# LTC6811_slave_12s_rev1.net
KiCad netlist of a schematic drawn in EAGLE
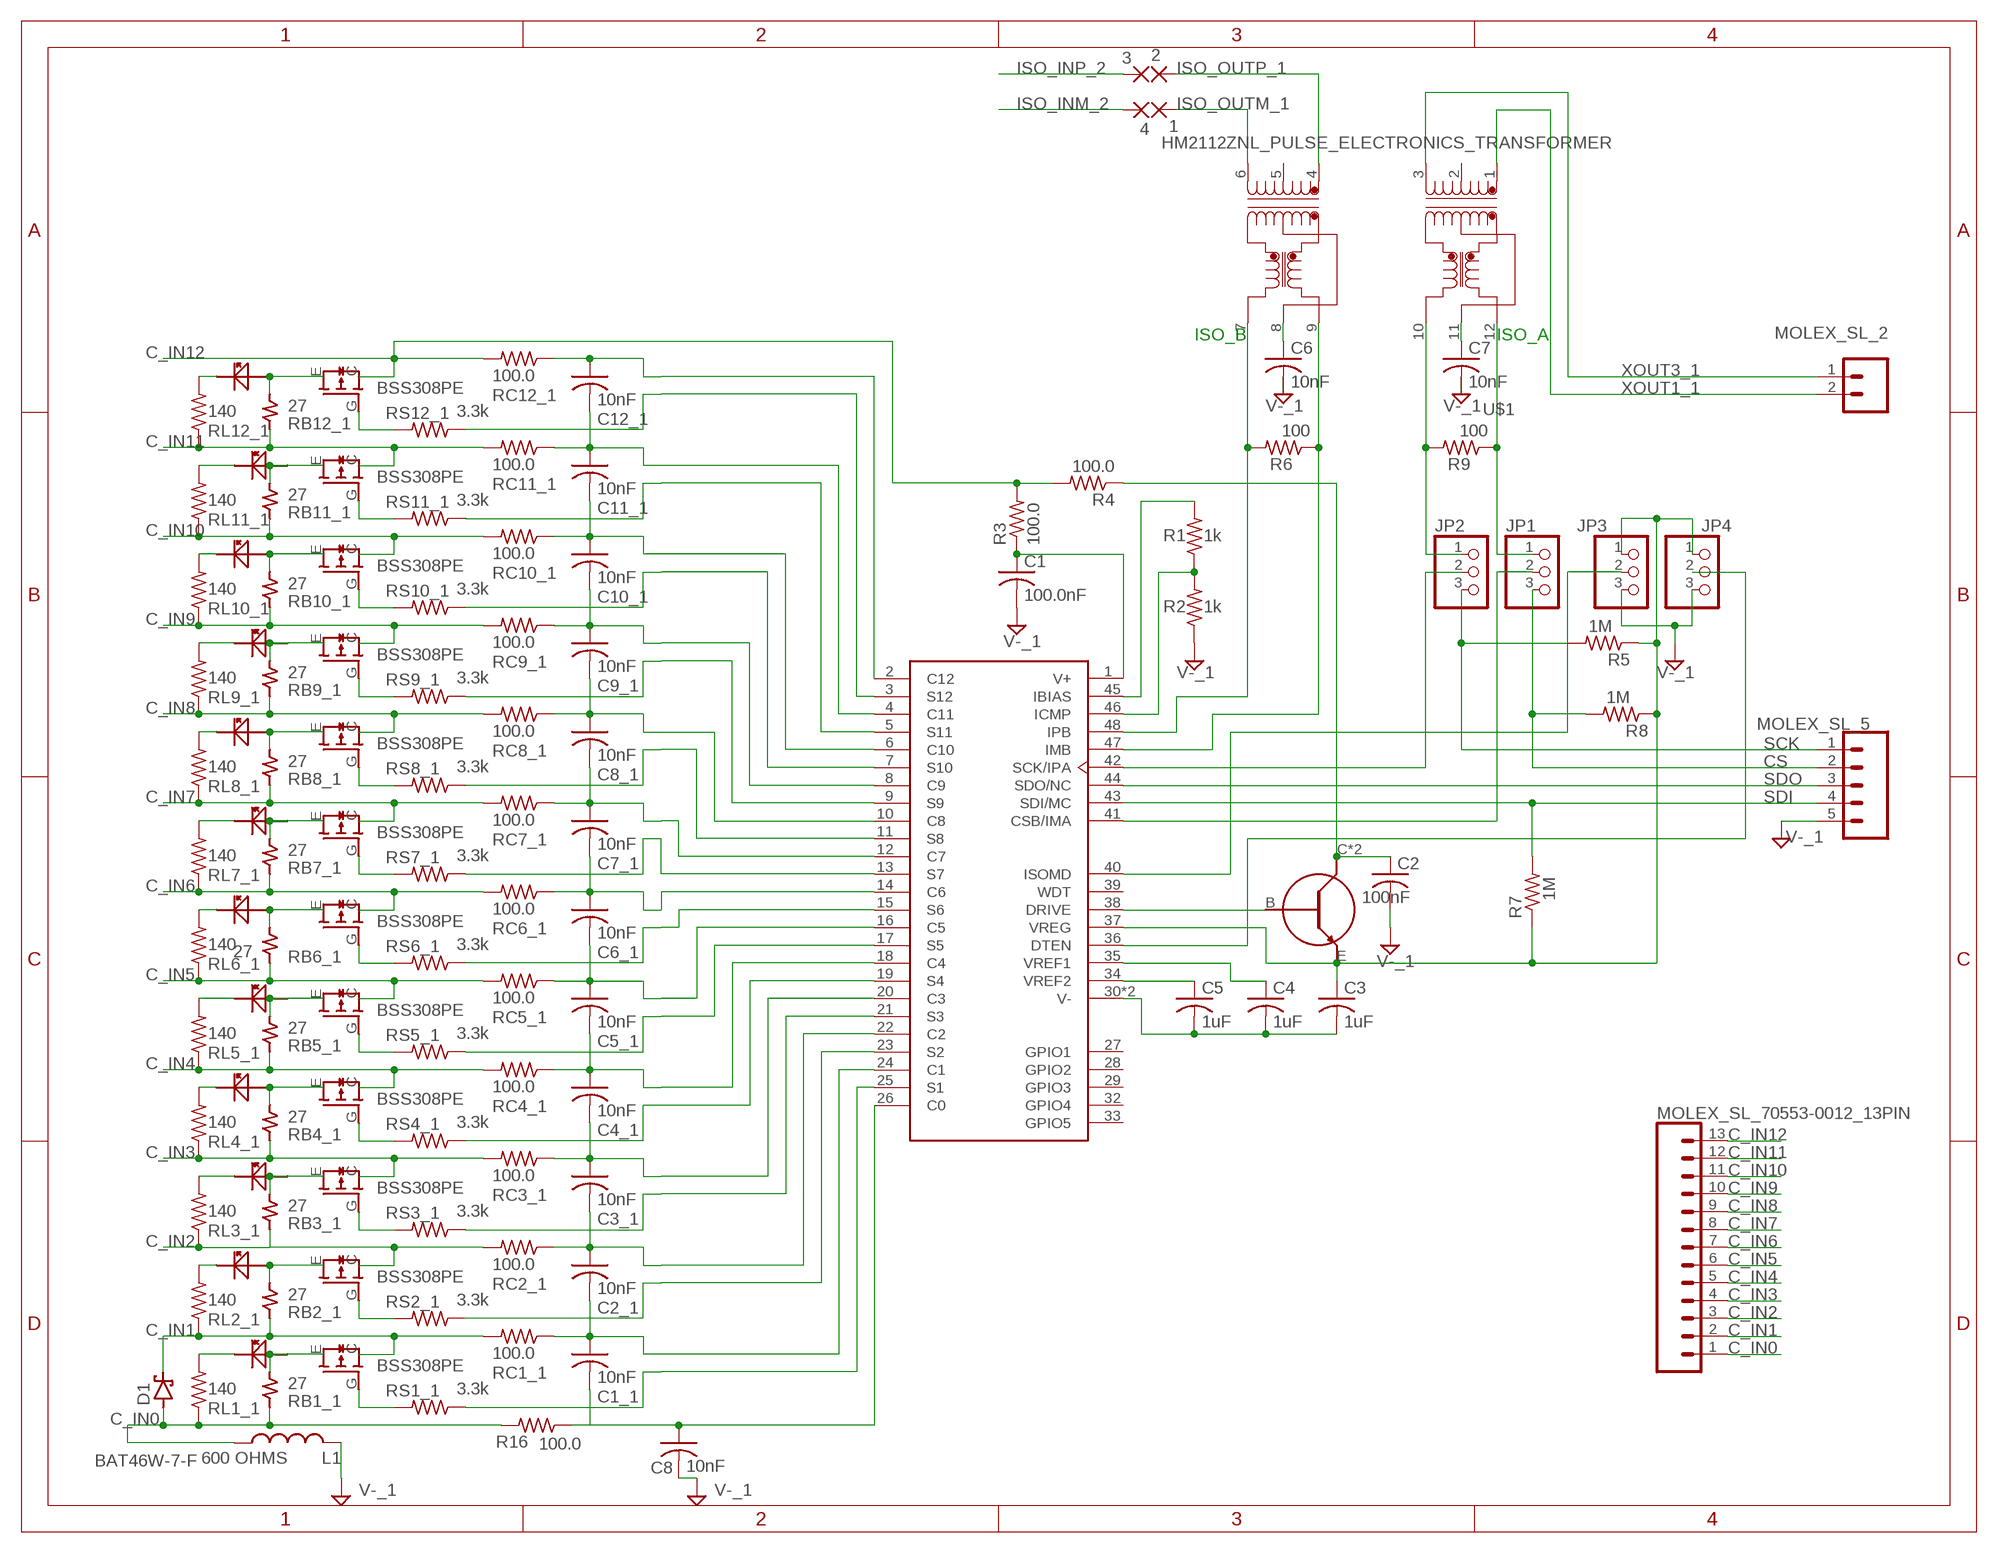
[diagram p0: schematic, sheet 1]

(export (version "E")
  (design (tool "Eeschema 10.0.6"))
  (components
    (comp (ref "1")
      (value "WIREPAD2,15/1,0")
      (footprint "eagle-import:2,15_1,0")
      (libsource (lib "eagle-import") (part "WIREPAD2,15/1,0"))
    )
    (comp (ref "2")
      (value "WIREPAD2,15/1,0")
      (footprint "eagle-import:2,15_1,0")
      (libsource (lib "eagle-import") (part "WIREPAD2,15/1,0"))
    )
    (comp (ref "3")
      (value "WIREPAD2,15/1,0")
      (footprint "eagle-import:2,15_1,0")
      (libsource (lib "eagle-import") (part "WIREPAD2,15/1,0"))
    )
    (comp (ref "4")
      (value "WIREPAD2,15/1,0")
      (footprint "eagle-import:2,15_1,0")
      (libsource (lib "eagle-import") (part "WIREPAD2,15/1,0"))
    )
    (comp (ref "C1")
      (value "100.0nF")
      (footprint "eagle-import:C0805")
      (libsource (lib "eagle-import") (part "C-USC0805"))
    )
    (comp (ref "C1_1")
      (value "10nF")
      (footprint "eagle-import:C0805")
      (libsource (lib "eagle-import") (part "C-USC0805"))
    )
    (comp (ref "C2")
      (value "100nF")
      (footprint "eagle-import:C0805")
      (libsource (lib "eagle-import") (part "C-USC0805"))
    )
    (comp (ref "C2_1")
      (value "10nF")
      (footprint "eagle-import:C0805")
      (libsource (lib "eagle-import") (part "C-USC0805"))
    )
    (comp (ref "C3")
      (value "1uF")
      (footprint "eagle-import:C0805")
      (libsource (lib "eagle-import") (part "C-USC0805"))
    )
    (comp (ref "C3_1")
      (value "10nF")
      (footprint "eagle-import:C0805")
      (libsource (lib "eagle-import") (part "C-USC0805"))
    )
    (comp (ref "C4")
      (value "1uF")
      (footprint "eagle-import:C0805")
      (libsource (lib "eagle-import") (part "C-USC0805"))
    )
    (comp (ref "C4_1")
      (value "10nF")
      (footprint "eagle-import:C0805")
      (libsource (lib "eagle-import") (part "C-USC0805"))
    )
    (comp (ref "C5")
      (value "1uF")
      (footprint "eagle-import:C0805")
      (libsource (lib "eagle-import") (part "C-USC0805"))
    )
    (comp (ref "C5_1")
      (value "10nF")
      (footprint "eagle-import:C0805")
      (libsource (lib "eagle-import") (part "C-USC0805"))
    )
    (comp (ref "C6")
      (value "10nF")
      (footprint "eagle-import:C0805")
      (libsource (lib "eagle-import") (part "C-USC0805"))
    )
    (comp (ref "C6_1")
      (value "10nF")
      (footprint "eagle-import:C0805")
      (libsource (lib "eagle-import") (part "C-USC0805"))
    )
    (comp (ref "C7")
      (value "10nF")
      (footprint "eagle-import:C0805")
      (libsource (lib "eagle-import") (part "C-USC0805"))
    )
    (comp (ref "C7_1")
      (value "10nF")
      (footprint "eagle-import:C0805")
      (libsource (lib "eagle-import") (part "C-USC0805"))
    )
    (comp (ref "C8")
      (value "10nF")
      (footprint "eagle-import:C0805")
      (libsource (lib "eagle-import") (part "C-USC0805"))
    )
    (comp (ref "C8_1")
      (value "10nF")
      (footprint "eagle-import:C0805")
      (libsource (lib "eagle-import") (part "C-USC0805"))
    )
    (comp (ref "C9_1")
      (value "10nF")
      (footprint "eagle-import:C0805")
      (libsource (lib "eagle-import") (part "C-USC0805"))
    )
    (comp (ref "C10_1")
      (value "10nF")
      (footprint "eagle-import:C0805")
      (libsource (lib "eagle-import") (part "C-USC0805"))
    )
    (comp (ref "C11_1")
      (value "10nF")
      (footprint "eagle-import:C0805")
      (libsource (lib "eagle-import") (part "C-USC0805"))
    )
    (comp (ref "C12_1")
      (value "10nF")
      (footprint "eagle-import:C0805")
      (libsource (lib "eagle-import") (part "C-USC0805"))
    )
    (comp (ref "D1")
      (value "BAT46W-7-F")
      (footprint "eagle-import:SOD123")
      (libsource (lib "eagle-import") (part "BAT46W-7-F"))
    )
    (comp (ref "DZT5551-13")
      (value "DZT5551-13")
      (footprint "eagle-import:SOT223-4")
      (libsource (lib "eagle-import") (part "DZT5551-13"))
    )
    (comp (ref "JP1")
      (value "PINHD-1X3")
      (footprint "eagle-import:1X03")
      (libsource (lib "eagle-import") (part "PINHD-1X3"))
    )
    (comp (ref "JP2")
      (value "PINHD-1X3")
      (footprint "eagle-import:1X03")
      (libsource (lib "eagle-import") (part "PINHD-1X3"))
    )
    (comp (ref "JP3")
      (value "PINHD-1X3")
      (footprint "eagle-import:1X03")
      (libsource (lib "eagle-import") (part "PINHD-1X3"))
    )
    (comp (ref "JP4")
      (value "PINHD-1X3")
      (footprint "eagle-import:1X03")
      (libsource (lib "eagle-import") (part "PINHD-1X3"))
    )
    (comp (ref "L1")
      (value "600 OHMS")
      (footprint "eagle-import:0805_COMPONENT")
      (libsource (lib "eagle-import") (part "0805_FERRITEBEAD_INDUCTOR"))
    )
    (comp (ref "LED1_3")
      (value "LED_0805")
      (footprint "eagle-import:0805_COMPONENT")
      (libsource (lib "eagle-import") (part "LED_0805"))
    )
    (comp (ref "LED1_4")
      (value "LED_0805")
      (footprint "eagle-import:0805_COMPONENT")
      (libsource (lib "eagle-import") (part "LED_0805"))
    )
    (comp (ref "LED1_5")
      (value "LED_0805")
      (footprint "eagle-import:0805_COMPONENT")
      (libsource (lib "eagle-import") (part "LED_0805"))
    )
    (comp (ref "LED1_6")
      (value "LED_0805")
      (footprint "eagle-import:0805_COMPONENT")
      (libsource (lib "eagle-import") (part "LED_0805"))
    )
    (comp (ref "LED1_7")
      (value "LED_0805")
      (footprint "eagle-import:0805_COMPONENT")
      (libsource (lib "eagle-import") (part "LED_0805"))
    )
    (comp (ref "LED1_8")
      (value "LED_0805")
      (footprint "eagle-import:0805_COMPONENT")
      (libsource (lib "eagle-import") (part "LED_0805"))
    )
    (comp (ref "LED1_9")
      (value "LED_0805")
      (footprint "eagle-import:0805_COMPONENT")
      (libsource (lib "eagle-import") (part "LED_0805"))
    )
    (comp (ref "LED1_10")
      (value "LED_0805")
      (footprint "eagle-import:0805_COMPONENT")
      (libsource (lib "eagle-import") (part "LED_0805"))
    )
    (comp (ref "LED1_11")
      (value "LED_0805")
      (footprint "eagle-import:0805_COMPONENT")
      (libsource (lib "eagle-import") (part "LED_0805"))
    )
    (comp (ref "LED1_12")
      (value "LED_0805")
      (footprint "eagle-import:0805_COMPONENT")
      (libsource (lib "eagle-import") (part "LED_0805"))
    )
    (comp (ref "LED1_13")
      (value "LED_0805")
      (footprint "eagle-import:0805_COMPONENT")
      (libsource (lib "eagle-import") (part "LED_0805"))
    )
    (comp (ref "LED1_14")
      (value "LED_0805")
      (footprint "eagle-import:0805_COMPONENT")
      (libsource (lib "eagle-import") (part "LED_0805"))
    )
    (comp (ref "MOLEX_SL_2")
      (value "CONN_02")
      (footprint "eagle-import:1X02")
      (libsource (lib "eagle-import") (part "CONN_02"))
    )
    (comp (ref "MOLEX_SL_5")
      (value "CONN_05")
      (footprint "eagle-import:1X05")
      (libsource (lib "eagle-import") (part "CONN_05"))
    )
    (comp (ref "MOLEX_SL_70553-0012_13PIN")
      (value "CONN_13")
      (footprint "eagle-import:1X13")
      (libsource (lib "eagle-import") (part "CONN_13"))
    )
    (comp (ref "R1")
      (value "1k")
      (footprint "eagle-import:R0805")
      (libsource (lib "eagle-import") (part "R-US_R0805"))
    )
    (comp (ref "R2")
      (value "1k")
      (footprint "eagle-import:R0805")
      (libsource (lib "eagle-import") (part "R-US_R0805"))
    )
    (comp (ref "R3")
      (value "100.0")
      (footprint "eagle-import:R0805")
      (libsource (lib "eagle-import") (part "R-US_R0805"))
    )
    (comp (ref "R4")
      (value "100.0")
      (footprint "eagle-import:R0805")
      (libsource (lib "eagle-import") (part "R-US_R0805"))
    )
    (comp (ref "R5")
      (value "1M")
      (footprint "eagle-import:R0805")
      (libsource (lib "eagle-import") (part "R-US_R0805"))
    )
    (comp (ref "R6")
      (value "100")
      (footprint "eagle-import:R0805")
      (libsource (lib "eagle-import") (part "R-US_R0805"))
    )
    (comp (ref "R7")
      (value "1M")
      (footprint "eagle-import:R0805")
      (libsource (lib "eagle-import") (part "R-US_R0805"))
    )
    (comp (ref "R8")
      (value "1M")
      (footprint "eagle-import:R0805")
      (libsource (lib "eagle-import") (part "R-US_R0805"))
    )
    (comp (ref "R9")
      (value "100")
      (footprint "eagle-import:R0805")
      (libsource (lib "eagle-import") (part "R-US_R0805"))
    )
    (comp (ref "R16")
      (value "100.0")
      (footprint "eagle-import:R0805")
      (libsource (lib "eagle-import") (part "R-US_R0805"))
    )
    (comp (ref "RB1_1")
      (value "27")
      (footprint "eagle-import:2817_COMPONENT")
      (libsource (lib "eagle-import") (part "2817_RESISTOR"))
    )
    (comp (ref "RB2_1")
      (value "27")
      (footprint "eagle-import:2817_COMPONENT")
      (libsource (lib "eagle-import") (part "2817_RESISTOR"))
    )
    (comp (ref "RB3_1")
      (value "27")
      (footprint "eagle-import:2817_COMPONENT")
      (libsource (lib "eagle-import") (part "2817_RESISTOR"))
    )
    (comp (ref "RB4_1")
      (value "27")
      (footprint "eagle-import:2817_COMPONENT")
      (libsource (lib "eagle-import") (part "2817_RESISTOR"))
    )
    (comp (ref "RB5_1")
      (value "27")
      (footprint "eagle-import:2817_COMPONENT")
      (libsource (lib "eagle-import") (part "2817_RESISTOR"))
    )
    (comp (ref "RB6_1")
      (value "27")
      (footprint "eagle-import:2817_COMPONENT")
      (libsource (lib "eagle-import") (part "2817_RESISTOR"))
    )
    (comp (ref "RB7_1")
      (value "27")
      (footprint "eagle-import:2817_COMPONENT")
      (libsource (lib "eagle-import") (part "2817_RESISTOR"))
    )
    (comp (ref "RB8_1")
      (value "27")
      (footprint "eagle-import:2817_COMPONENT")
      (libsource (lib "eagle-import") (part "2817_RESISTOR"))
    )
    (comp (ref "RB9_1")
      (value "27")
      (footprint "eagle-import:2817_COMPONENT")
      (libsource (lib "eagle-import") (part "2817_RESISTOR"))
    )
    (comp (ref "RB10_1")
      (value "27")
      (footprint "eagle-import:2817_COMPONENT")
      (libsource (lib "eagle-import") (part "2817_RESISTOR"))
    )
    (comp (ref "RB11_1")
      (value "27")
      (footprint "eagle-import:2817_COMPONENT")
      (libsource (lib "eagle-import") (part "2817_RESISTOR"))
    )
    (comp (ref "RB12_1")
      (value "27")
      (footprint "eagle-import:2817_COMPONENT")
      (libsource (lib "eagle-import") (part "2817_RESISTOR"))
    )
    (comp (ref "RC1_1")
      (value "100.0")
      (footprint "eagle-import:R0805")
      (libsource (lib "eagle-import") (part "R-US_R0805"))
    )
    (comp (ref "RC2_1")
      (value "100.0")
      (footprint "eagle-import:R0805")
      (libsource (lib "eagle-import") (part "R-US_R0805"))
    )
    (comp (ref "RC3_1")
      (value "100.0")
      (footprint "eagle-import:R0805")
      (libsource (lib "eagle-import") (part "R-US_R0805"))
    )
    (comp (ref "RC4_1")
      (value "100.0")
      (footprint "eagle-import:R0805")
      (libsource (lib "eagle-import") (part "R-US_R0805"))
    )
    (comp (ref "RC5_1")
      (value "100.0")
      (footprint "eagle-import:R0805")
      (libsource (lib "eagle-import") (part "R-US_R0805"))
    )
    (comp (ref "RC6_1")
      (value "100.0")
      (footprint "eagle-import:R0805")
      (libsource (lib "eagle-import") (part "R-US_R0805"))
    )
    (comp (ref "RC7_1")
      (value "100.0")
      (footprint "eagle-import:R0805")
      (libsource (lib "eagle-import") (part "R-US_R0805"))
    )
    (comp (ref "RC8_1")
      (value "100.0")
      (footprint "eagle-import:R0805")
      (libsource (lib "eagle-import") (part "R-US_R0805"))
    )
    (comp (ref "RC9_1")
      (value "100.0")
      (footprint "eagle-import:R0805")
      (libsource (lib "eagle-import") (part "R-US_R0805"))
    )
    (comp (ref "RC10_1")
      (value "100.0")
      (footprint "eagle-import:R0805")
      (libsource (lib "eagle-import") (part "R-US_R0805"))
    )
    (comp (ref "RC11_1")
      (value "100.0")
      (footprint "eagle-import:R0805")
      (libsource (lib "eagle-import") (part "R-US_R0805"))
    )
    (comp (ref "RC12_1")
      (value "100.0")
      (footprint "eagle-import:R0805")
      (libsource (lib "eagle-import") (part "R-US_R0805"))
    )
    (comp (ref "RL1_1")
      (value "140")
      (footprint "eagle-import:R0805")
      (libsource (lib "eagle-import") (part "R-US_R0805"))
    )
    (comp (ref "RL2_1")
      (value "140")
      (footprint "eagle-import:R0805")
      (libsource (lib "eagle-import") (part "R-US_R0805"))
    )
    (comp (ref "RL3_1")
      (value "140")
      (footprint "eagle-import:R0805")
      (libsource (lib "eagle-import") (part "R-US_R0805"))
    )
    (comp (ref "RL4_1")
      (value "140")
      (footprint "eagle-import:R0805")
      (libsource (lib "eagle-import") (part "R-US_R0805"))
    )
    (comp (ref "RL5_1")
      (value "140")
      (footprint "eagle-import:R0805")
      (libsource (lib "eagle-import") (part "R-US_R0805"))
    )
    (comp (ref "RL6_1")
      (value "140")
      (footprint "eagle-import:R0805")
      (libsource (lib "eagle-import") (part "R-US_R0805"))
    )
    (comp (ref "RL7_1")
      (value "140")
      (footprint "eagle-import:R0805")
      (libsource (lib "eagle-import") (part "R-US_R0805"))
    )
    (comp (ref "RL8_1")
      (value "140")
      (footprint "eagle-import:R0805")
      (libsource (lib "eagle-import") (part "R-US_R0805"))
    )
    (comp (ref "RL9_1")
      (value "140")
      (footprint "eagle-import:R0805")
      (libsource (lib "eagle-import") (part "R-US_R0805"))
    )
    (comp (ref "RL10_1")
      (value "140")
      (footprint "eagle-import:R0805")
      (libsource (lib "eagle-import") (part "R-US_R0805"))
    )
    (comp (ref "RL11_1")
      (value "140")
      (footprint "eagle-import:R0805")
      (libsource (lib "eagle-import") (part "R-US_R0805"))
    )
    (comp (ref "RL12_1")
      (value "140")
      (footprint "eagle-import:R0805")
      (libsource (lib "eagle-import") (part "R-US_R0805"))
    )
    (comp (ref "RS1_1")
      (value "3.3k")
      (footprint "eagle-import:R0805")
      (libsource (lib "eagle-import") (part "R-US_R0805"))
    )
    (comp (ref "RS2_1")
      (value "3.3k")
      (footprint "eagle-import:R0805")
      (libsource (lib "eagle-import") (part "R-US_R0805"))
    )
    (comp (ref "RS3_1")
      (value "3.3k")
      (footprint "eagle-import:R0805")
      (libsource (lib "eagle-import") (part "R-US_R0805"))
    )
    (comp (ref "RS4_1")
      (value "3.3k")
      (footprint "eagle-import:R0805")
      (libsource (lib "eagle-import") (part "R-US_R0805"))
    )
    (comp (ref "RS5_1")
      (value "3.3k")
      (footprint "eagle-import:R0805")
      (libsource (lib "eagle-import") (part "R-US_R0805"))
    )
    (comp (ref "RS6_1")
      (value "3.3k")
      (footprint "eagle-import:R0805")
      (libsource (lib "eagle-import") (part "R-US_R0805"))
    )
    (comp (ref "RS7_1")
      (value "3.3k")
      (footprint "eagle-import:R0805")
      (libsource (lib "eagle-import") (part "R-US_R0805"))
    )
    (comp (ref "RS8_1")
      (value "3.3k")
      (footprint "eagle-import:R0805")
      (libsource (lib "eagle-import") (part "R-US_R0805"))
    )
    (comp (ref "RS9_1")
      (value "3.3k")
      (footprint "eagle-import:R0805")
      (libsource (lib "eagle-import") (part "R-US_R0805"))
    )
    (comp (ref "RS10_1")
      (value "3.3k")
      (footprint "eagle-import:R0805")
      (libsource (lib "eagle-import") (part "R-US_R0805"))
    )
    (comp (ref "RS11_1")
      (value "3.3k")
      (footprint "eagle-import:R0805")
      (libsource (lib "eagle-import") (part "R-US_R0805"))
    )
    (comp (ref "RS12_1")
      (value "3.3k")
      (footprint "eagle-import:R0805")
      (libsource (lib "eagle-import") (part "R-US_R0805"))
    )
    (comp (ref "T1_3")
      (value "BSS308PEH6327")
      (footprint "eagle-import:SOT23")
      (libsource (lib "eagle-import") (part "BSS308PEH6327"))
    )
    (comp (ref "T1_4")
      (value "BSS308PEH6327")
      (footprint "eagle-import:SOT23")
      (libsource (lib "eagle-import") (part "BSS308PEH6327"))
    )
    (comp (ref "T1_5")
      (value "BSS308PEH6327")
      (footprint "eagle-import:SOT23")
      (libsource (lib "eagle-import") (part "BSS308PEH6327"))
    )
    (comp (ref "T1_6")
      (value "BSS308PEH6327")
      (footprint "eagle-import:SOT23")
      (libsource (lib "eagle-import") (part "BSS308PEH6327"))
    )
    (comp (ref "T1_7")
      (value "BSS308PEH6327")
      (footprint "eagle-import:SOT23")
      (libsource (lib "eagle-import") (part "BSS308PEH6327"))
    )
    (comp (ref "T1_8")
      (value "BSS308PEH6327")
      (footprint "eagle-import:SOT23")
      (libsource (lib "eagle-import") (part "BSS308PEH6327"))
    )
    (comp (ref "T1_9")
      (value "BSS308PEH6327")
      (footprint "eagle-import:SOT23")
      (libsource (lib "eagle-import") (part "BSS308PEH6327"))
    )
    (comp (ref "T1_10")
      (value "BSS308PEH6327")
      (footprint "eagle-import:SOT23")
      (libsource (lib "eagle-import") (part "BSS308PEH6327"))
    )
    (comp (ref "T1_11")
      (value "BSS308PEH6327")
      (footprint "eagle-import:SOT23")
      (libsource (lib "eagle-import") (part "BSS308PEH6327"))
    )
    (comp (ref "T1_12")
      (value "BSS308PEH6327")
      (footprint "eagle-import:SOT23")
      (libsource (lib "eagle-import") (part "BSS308PEH6327"))
    )
    (comp (ref "T1_13")
      (value "BSS308PEH6327")
      (footprint "eagle-import:SOT23")
      (libsource (lib "eagle-import") (part "BSS308PEH6327"))
    )
    (comp (ref "T1_14")
      (value "BSS308PEH6327")
      (footprint "eagle-import:SOT23")
      (libsource (lib "eagle-import") (part "BSS308PEH6327"))
    )
    (comp (ref "U$1")
      (value "HM2112ZNL_PULSE_ELECTRONICS_TRANSFORMER")
      (footprint "eagle-import:HM2112ZNL_12SMT")
      (libsource (lib "eagle-import") (part "HM2112ZNL_PULSE_ELECTRONICS_TRANSFORMER"))
    )
    (comp (ref "U1")
      (value "LTC6811HG-2#PBF")
      (footprint "eagle-import:LTC6811-1")
      (fields (field (name "MF") "Linear Technology/Analog"))
      (libsource (lib "eagle-import") (part "LTC6811HG-2#PBF"))
    )
  )
  (nets
    (net (code "1") (name "C2") (class "Default")
      (node (ref "C2_1") (pin "1") (pinfunction "1_1") (pintype "passive"))
      (node (ref "C3_1") (pin "2") (pinfunction "2_2") (pintype "passive"))
      (node (ref "RC2_1") (pin "1") (pinfunction "1_1") (pintype "passive"))
      (node (ref "U1") (pin "22") (pinfunction "C2_22") (pintype "input"))
    )
    (net (code "2") (name "C4") (class "Default")
      (node (ref "C4_1") (pin "1") (pinfunction "1_1") (pintype "passive"))
      (node (ref "C5_1") (pin "2") (pinfunction "2_2") (pintype "passive"))
      (node (ref "RC4_1") (pin "1") (pinfunction "1_1") (pintype "passive"))
      (node (ref "U1") (pin "18") (pinfunction "C4_18") (pintype "input"))
    )
    (net (code "3") (name "C6") (class "Default")
      (node (ref "C6_1") (pin "1") (pinfunction "1_1") (pintype "passive"))
      (node (ref "C7_1") (pin "2") (pinfunction "2_2") (pintype "passive"))
      (node (ref "RC6_1") (pin "1") (pinfunction "1_1") (pintype "passive"))
      (node (ref "U1") (pin "14") (pinfunction "C6_14") (pintype "input"))
    )
    (net (code "4") (name "C8") (class "Default")
      (node (ref "C8_1") (pin "1") (pinfunction "1_1") (pintype "passive"))
      (node (ref "C9_1") (pin "2") (pinfunction "2_2") (pintype "passive"))
      (node (ref "RC8_1") (pin "1") (pinfunction "1_1") (pintype "passive"))
      (node (ref "U1") (pin "10") (pinfunction "C8_10") (pintype "input"))
    )
    (net (code "5") (name "CS") (class "Default")
      (node (ref "JP1") (pin "3") (pinfunction "3_3") (pintype "passive"))
      (node (ref "MOLEX_SL_5") (pin "2") (pinfunction "2_2") (pintype "passive"))
      (node (ref "R8") (pin "2") (pinfunction "2_2") (pintype "passive"))
    )
    (net (code "6") (name "C_IN0") (class "Default")
      (node (ref "D1") (pin "A") (pinfunction "A_A") (pintype "passive"))
      (node (ref "L1") (pin "1") (pinfunction "1_1") (pintype "passive"))
      (node (ref "MOLEX_SL_70553-0012_13PIN") (pin "1") (pinfunction "1_1") (pintype "passive"))
      (node (ref "R16") (pin "2") (pinfunction "2_2") (pintype "passive"))
      (node (ref "RB1_1") (pin "2") (pinfunction "P$2_2") (pintype "bidirectional"))
      (node (ref "RL1_1") (pin "1") (pinfunction "1_1") (pintype "passive"))
    )
    (net (code "7") (name "C_IN1") (class "Default")
      (node (ref "D1") (pin "C") (pinfunction "C_C") (pintype "passive"))
      (node (ref "MOLEX_SL_70553-0012_13PIN") (pin "2") (pinfunction "2_2") (pintype "passive"))
      (node (ref "RB2_1") (pin "2") (pinfunction "P$2_2") (pintype "bidirectional"))
      (node (ref "RC1_1") (pin "2") (pinfunction "2_2") (pintype "passive"))
      (node (ref "RL2_1") (pin "1") (pinfunction "1_1") (pintype "passive"))
      (node (ref "T1_3") (pin "C") (pinfunction "C_C") (pintype "bidirectional"))
    )
    (net (code "8") (name "C_IN2") (class "Default")
      (node (ref "MOLEX_SL_70553-0012_13PIN") (pin "3") (pinfunction "3_3") (pintype "passive"))
      (node (ref "RB3_1") (pin "2") (pinfunction "P$2_2") (pintype "bidirectional"))
      (node (ref "RC2_1") (pin "2") (pinfunction "2_2") (pintype "passive"))
      (node (ref "RL3_1") (pin "1") (pinfunction "1_1") (pintype "passive"))
      (node (ref "T1_4") (pin "C") (pinfunction "C_C") (pintype "bidirectional"))
    )
    (net (code "9") (name "C_IN3") (class "Default")
      (node (ref "MOLEX_SL_70553-0012_13PIN") (pin "4") (pinfunction "4_4") (pintype "passive"))
      (node (ref "RB4_1") (pin "2") (pinfunction "P$2_2") (pintype "bidirectional"))
      (node (ref "RC3_1") (pin "2") (pinfunction "2_2") (pintype "passive"))
      (node (ref "RL4_1") (pin "1") (pinfunction "1_1") (pintype "passive"))
      (node (ref "T1_7") (pin "C") (pinfunction "C_C") (pintype "bidirectional"))
    )
    (net (code "10") (name "C_IN4") (class "Default")
      (node (ref "MOLEX_SL_70553-0012_13PIN") (pin "5") (pinfunction "5_5") (pintype "passive"))
      (node (ref "RB5_1") (pin "2") (pinfunction "P$2_2") (pintype "bidirectional"))
      (node (ref "RC4_1") (pin "2") (pinfunction "2_2") (pintype "passive"))
      (node (ref "RL5_1") (pin "1") (pinfunction "1_1") (pintype "passive"))
      (node (ref "T1_8") (pin "C") (pinfunction "C_C") (pintype "bidirectional"))
    )
    (net (code "11") (name "C_IN5") (class "Default")
      (node (ref "MOLEX_SL_70553-0012_13PIN") (pin "6") (pinfunction "6_6") (pintype "passive"))
      (node (ref "RB6_1") (pin "2") (pinfunction "P$2_2") (pintype "bidirectional"))
      (node (ref "RC5_1") (pin "2") (pinfunction "2_2") (pintype "passive"))
      (node (ref "RL6_1") (pin "1") (pinfunction "1_1") (pintype "passive"))
      (node (ref "T1_5") (pin "C") (pinfunction "C_C") (pintype "bidirectional"))
    )
    (net (code "12") (name "C_IN6") (class "Default")
      (node (ref "MOLEX_SL_70553-0012_13PIN") (pin "7") (pinfunction "7_7") (pintype "passive"))
      (node (ref "RB7_1") (pin "2") (pinfunction "P$2_2") (pintype "bidirectional"))
      (node (ref "RC6_1") (pin "2") (pinfunction "2_2") (pintype "passive"))
      (node (ref "RL7_1") (pin "1") (pinfunction "1_1") (pintype "passive"))
      (node (ref "T1_6") (pin "C") (pinfunction "C_C") (pintype "bidirectional"))
    )
    (net (code "13") (name "C_IN7") (class "Default")
      (node (ref "MOLEX_SL_70553-0012_13PIN") (pin "8") (pinfunction "8_8") (pintype "passive"))
      (node (ref "RB8_1") (pin "2") (pinfunction "P$2_2") (pintype "bidirectional"))
      (node (ref "RC7_1") (pin "2") (pinfunction "2_2") (pintype "passive"))
      (node (ref "RL8_1") (pin "1") (pinfunction "1_1") (pintype "passive"))
      (node (ref "T1_9") (pin "C") (pinfunction "C_C") (pintype "bidirectional"))
    )
    (net (code "14") (name "C_IN8") (class "Default")
      (node (ref "MOLEX_SL_70553-0012_13PIN") (pin "9") (pinfunction "9_9") (pintype "passive"))
      (node (ref "RB9_1") (pin "2") (pinfunction "P$2_2") (pintype "bidirectional"))
      (node (ref "RC8_1") (pin "2") (pinfunction "2_2") (pintype "passive"))
      (node (ref "RL9_1") (pin "1") (pinfunction "1_1") (pintype "passive"))
      (node (ref "T1_10") (pin "C") (pinfunction "C_C") (pintype "bidirectional"))
    )
    (net (code "15") (name "C_IN9") (class "Default")
      (node (ref "MOLEX_SL_70553-0012_13PIN") (pin "10") (pinfunction "10_10") (pintype "passive"))
      (node (ref "RB10_1") (pin "2") (pinfunction "P$2_2") (pintype "bidirectional"))
      (node (ref "RC9_1") (pin "2") (pinfunction "2_2") (pintype "passive"))
      (node (ref "RL10_1") (pin "1") (pinfunction "1_1") (pintype "passive"))
      (node (ref "T1_11") (pin "C") (pinfunction "C_C") (pintype "bidirectional"))
    )
    (net (code "16") (name "C_IN10") (class "Default")
      (node (ref "MOLEX_SL_70553-0012_13PIN") (pin "11") (pinfunction "11_11") (pintype "passive"))
      (node (ref "RB11_1") (pin "2") (pinfunction "P$2_2") (pintype "bidirectional"))
      (node (ref "RC10_1") (pin "2") (pinfunction "2_2") (pintype "passive"))
      (node (ref "RL11_1") (pin "1") (pinfunction "1_1") (pintype "passive"))
      (node (ref "T1_12") (pin "C") (pinfunction "C_C") (pintype "bidirectional"))
    )
    (net (code "17") (name "C_IN11") (class "Default")
      (node (ref "MOLEX_SL_70553-0012_13PIN") (pin "12") (pinfunction "12_12") (pintype "passive"))
      (node (ref "RB12_1") (pin "2") (pinfunction "P$2_2") (pintype "bidirectional"))
      (node (ref "RC11_1") (pin "2") (pinfunction "2_2") (pintype "passive"))
      (node (ref "RL12_1") (pin "1") (pinfunction "1_1") (pintype "passive"))
      (node (ref "T1_13") (pin "C") (pinfunction "C_C") (pintype "bidirectional"))
    )
    (net (code "18") (name "C_IN12") (class "Default")
      (node (ref "MOLEX_SL_70553-0012_13PIN") (pin "13") (pinfunction "13_13") (pintype "passive"))
      (node (ref "R3") (pin "2") (pinfunction "2_2") (pintype "passive"))
      (node (ref "R4") (pin "2") (pinfunction "2_2") (pintype "passive"))
      (node (ref "RC12_1") (pin "2") (pinfunction "2_2") (pintype "passive"))
      (node (ref "T1_14") (pin "C") (pinfunction "C_C") (pintype "bidirectional"))
    )
    (net (code "19") (name "ISO_INM_2") (class "Default")
      (node (ref "4") (pin "1") (pinfunction "P_1") (pintype "passive"))
    )
    (net (code "20") (name "ISO_INP_2") (class "Default")
      (node (ref "3") (pin "1") (pinfunction "P_1") (pintype "passive"))
    )
    (net (code "21") (name "ISO_OUTM_1") (class "Default")
      (node (ref "1") (pin "1") (pinfunction "P_1") (pintype "passive"))
      (node (ref "U$1") (pin "6") (pinfunction "6_6") (pintype "bidirectional"))
    )
    (net (code "22") (name "ISO_OUTP_1") (class "Default")
      (node (ref "2") (pin "1") (pinfunction "P_1") (pintype "passive"))
      (node (ref "U$1") (pin "4") (pinfunction "4_4") (pintype "bidirectional"))
    )
    (net (code "23") (name "Net-(C2-Pad1)") (class "Default")
      (node (ref "C2") (pin "1") (pinfunction "1_1") (pintype "passive"))
      (node (ref "DZT5551-13") (pin "C") (pinfunction "C_C") (pintype "bidirectional"))
      (node (ref "DZT5551-13") (pin "C@2") (pinfunction "C_C@2") (pintype "bidirectional"))
      (node (ref "R4") (pin "1") (pinfunction "1_1") (pintype "passive"))
    )
    (net (code "24") (name "Net-(C6-Pad1)") (class "Default")
      (node (ref "C6") (pin "1") (pinfunction "1_1") (pintype "passive"))
      (node (ref "U$1") (pin "8") (pinfunction "8_8") (pintype "bidirectional"))
    )
    (net (code "25") (name "Net-(C7-Pad1)") (class "Default")
      (node (ref "C7") (pin "1") (pinfunction "1_1") (pintype "passive"))
      (node (ref "U$1") (pin "11") (pinfunction "11_11") (pintype "bidirectional"))
    )
    (net (code "26") (name "Net-(JP1-Pad1)") (class "Default")
      (node (ref "JP1") (pin "1") (pinfunction "1_1") (pintype "passive"))
      (node (ref "R9") (pin "1") (pinfunction "1_1") (pintype "passive"))
      (node (ref "U$1") (pin "12") (pinfunction "12_12") (pintype "bidirectional"))
    )
    (net (code "27") (name "Net-(JP2-Pad1)") (class "Default")
      (node (ref "JP2") (pin "1") (pinfunction "1_1") (pintype "passive"))
      (node (ref "R9") (pin "2") (pinfunction "2_2") (pintype "passive"))
      (node (ref "U$1") (pin "10") (pinfunction "10_10") (pintype "bidirectional"))
    )
    (net (code "28") (name "Net-(LED1_3-P$1)") (class "Default")
      (node (ref "LED1_3") (pin "1") (pinfunction "P$1_1") (pintype "bidirectional"))
      (node (ref "RL1_1") (pin "2") (pinfunction "2_2") (pintype "passive"))
    )
    (net (code "29") (name "Net-(LED1_3-P$2)") (class "Default")
      (node (ref "LED1_3") (pin "2") (pinfunction "P$2_2") (pintype "bidirectional"))
      (node (ref "RB1_1") (pin "1") (pinfunction "P$1_1") (pintype "bidirectional"))
      (node (ref "T1_3") (pin "E") (pinfunction "E_E") (pintype "bidirectional"))
    )
    (net (code "30") (name "Net-(LED1_4-P$1)") (class "Default")
      (node (ref "LED1_4") (pin "1") (pinfunction "P$1_1") (pintype "bidirectional"))
      (node (ref "RL2_1") (pin "2") (pinfunction "2_2") (pintype "passive"))
    )
    (net (code "31") (name "Net-(LED1_4-P$2)") (class "Default")
      (node (ref "LED1_4") (pin "2") (pinfunction "P$2_2") (pintype "bidirectional"))
      (node (ref "RB2_1") (pin "1") (pinfunction "P$1_1") (pintype "bidirectional"))
      (node (ref "T1_4") (pin "E") (pinfunction "E_E") (pintype "bidirectional"))
    )
    (net (code "32") (name "Net-(LED1_5-P$1)") (class "Default")
      (node (ref "LED1_5") (pin "1") (pinfunction "P$1_1") (pintype "bidirectional"))
      (node (ref "RL5_1") (pin "2") (pinfunction "2_2") (pintype "passive"))
    )
    (net (code "33") (name "Net-(LED1_5-P$2)") (class "Default")
      (node (ref "LED1_5") (pin "2") (pinfunction "P$2_2") (pintype "bidirectional"))
      (node (ref "RB5_1") (pin "1") (pinfunction "P$1_1") (pintype "bidirectional"))
      (node (ref "T1_5") (pin "E") (pinfunction "E_E") (pintype "bidirectional"))
    )
    (net (code "34") (name "Net-(LED1_6-P$1)") (class "Default")
      (node (ref "LED1_6") (pin "1") (pinfunction "P$1_1") (pintype "bidirectional"))
      (node (ref "RL6_1") (pin "2") (pinfunction "2_2") (pintype "passive"))
    )
    (net (code "35") (name "Net-(LED1_6-P$2)") (class "Default")
      (node (ref "LED1_6") (pin "2") (pinfunction "P$2_2") (pintype "bidirectional"))
      (node (ref "RB6_1") (pin "1") (pinfunction "P$1_1") (pintype "bidirectional"))
      (node (ref "T1_6") (pin "E") (pinfunction "E_E") (pintype "bidirectional"))
    )
    (net (code "36") (name "Net-(LED1_7-P$1)") (class "Default")
      (node (ref "LED1_7") (pin "1") (pinfunction "P$1_1") (pintype "bidirectional"))
      (node (ref "RL3_1") (pin "2") (pinfunction "2_2") (pintype "passive"))
    )
    (net (code "37") (name "Net-(LED1_7-P$2)") (class "Default")
      (node (ref "LED1_7") (pin "2") (pinfunction "P$2_2") (pintype "bidirectional"))
      (node (ref "RB3_1") (pin "1") (pinfunction "P$1_1") (pintype "bidirectional"))
      (node (ref "T1_7") (pin "E") (pinfunction "E_E") (pintype "bidirectional"))
    )
    (net (code "38") (name "Net-(LED1_8-P$1)") (class "Default")
      (node (ref "LED1_8") (pin "1") (pinfunction "P$1_1") (pintype "bidirectional"))
      (node (ref "RL4_1") (pin "2") (pinfunction "2_2") (pintype "passive"))
    )
    (net (code "39") (name "Net-(LED1_8-P$2)") (class "Default")
      (node (ref "LED1_8") (pin "2") (pinfunction "P$2_2") (pintype "bidirectional"))
      (node (ref "RB4_1") (pin "1") (pinfunction "P$1_1") (pintype "bidirectional"))
      (node (ref "T1_8") (pin "E") (pinfunction "E_E") (pintype "bidirectional"))
    )
    (net (code "40") (name "Net-(LED1_9-P$1)") (class "Default")
      (node (ref "LED1_9") (pin "1") (pinfunction "P$1_1") (pintype "bidirectional"))
      (node (ref "RL7_1") (pin "2") (pinfunction "2_2") (pintype "passive"))
    )
    (net (code "41") (name "Net-(LED1_9-P$2)") (class "Default")
      (node (ref "LED1_9") (pin "2") (pinfunction "P$2_2") (pintype "bidirectional"))
      (node (ref "RB7_1") (pin "1") (pinfunction "P$1_1") (pintype "bidirectional"))
      (node (ref "T1_9") (pin "E") (pinfunction "E_E") (pintype "bidirectional"))
    )
    (net (code "42") (name "Net-(LED1_10-P$1)") (class "Default")
      (node (ref "LED1_10") (pin "1") (pinfunction "P$1_1") (pintype "bidirectional"))
      (node (ref "RL8_1") (pin "2") (pinfunction "2_2") (pintype "passive"))
    )
    (net (code "43") (name "Net-(LED1_10-P$2)") (class "Default")
      (node (ref "LED1_10") (pin "2") (pinfunction "P$2_2") (pintype "bidirectional"))
      (node (ref "RB8_1") (pin "1") (pinfunction "P$1_1") (pintype "bidirectional"))
      (node (ref "T1_10") (pin "E") (pinfunction "E_E") (pintype "bidirectional"))
    )
    (net (code "44") (name "Net-(LED1_11-P$1)") (class "Default")
      (node (ref "LED1_11") (pin "1") (pinfunction "P$1_1") (pintype "bidirectional"))
      (node (ref "RL9_1") (pin "2") (pinfunction "2_2") (pintype "passive"))
    )
    (net (code "45") (name "Net-(LED1_11-P$2)") (class "Default")
      (node (ref "LED1_11") (pin "2") (pinfunction "P$2_2") (pintype "bidirectional"))
      (node (ref "RB9_1") (pin "1") (pinfunction "P$1_1") (pintype "bidirectional"))
      (node (ref "T1_11") (pin "E") (pinfunction "E_E") (pintype "bidirectional"))
    )
    (net (code "46") (name "Net-(LED1_12-P$1)") (class "Default")
      (node (ref "LED1_12") (pin "1") (pinfunction "P$1_1") (pintype "bidirectional"))
      (node (ref "RL10_1") (pin "2") (pinfunction "2_2") (pintype "passive"))
    )
    (net (code "47") (name "Net-(LED1_12-P$2)") (class "Default")
      (node (ref "LED1_12") (pin "2") (pinfunction "P$2_2") (pintype "bidirectional"))
      (node (ref "RB10_1") (pin "1") (pinfunction "P$1_1") (pintype "bidirectional"))
      (node (ref "T1_12") (pin "E") (pinfunction "E_E") (pintype "bidirectional"))
    )
    (net (code "48") (name "Net-(LED1_13-P$1)") (class "Default")
      (node (ref "LED1_13") (pin "1") (pinfunction "P$1_1") (pintype "bidirectional"))
      (node (ref "RL11_1") (pin "2") (pinfunction "2_2") (pintype "passive"))
    )
    (net (code "49") (name "Net-(LED1_13-P$2)") (class "Default")
      (node (ref "LED1_13") (pin "2") (pinfunction "P$2_2") (pintype "bidirectional"))
      (node (ref "RB11_1") (pin "1") (pinfunction "P$1_1") (pintype "bidirectional"))
      (node (ref "T1_13") (pin "E") (pinfunction "E_E") (pintype "bidirectional"))
    )
    (net (code "50") (name "Net-(LED1_14-P$1)") (class "Default")
      (node (ref "LED1_14") (pin "1") (pinfunction "P$1_1") (pintype "bidirectional"))
      (node (ref "RL12_1") (pin "2") (pinfunction "2_2") (pintype "passive"))
    )
    (net (code "51") (name "Net-(LED1_14-P$2)") (class "Default")
      (node (ref "LED1_14") (pin "2") (pinfunction "P$2_2") (pintype "bidirectional"))
      (node (ref "RB12_1") (pin "1") (pinfunction "P$1_1") (pintype "bidirectional"))
      (node (ref "T1_14") (pin "E") (pinfunction "E_E") (pintype "bidirectional"))
    )
    (net (code "52") (name "Net-(T1_3-B)") (class "Default")
      (node (ref "RS1_1") (pin "2") (pinfunction "2_2") (pintype "passive"))
      (node (ref "T1_3") (pin "G") (pinfunction "B_G") (pintype "bidirectional"))
    )
    (net (code "53") (name "Net-(T1_4-B)") (class "Default")
      (node (ref "RS2_1") (pin "2") (pinfunction "2_2") (pintype "passive"))
      (node (ref "T1_4") (pin "G") (pinfunction "B_G") (pintype "bidirectional"))
    )
    (net (code "54") (name "Net-(T1_5-B)") (class "Default")
      (node (ref "RS5_1") (pin "2") (pinfunction "2_2") (pintype "passive"))
      (node (ref "T1_5") (pin "G") (pinfunction "B_G") (pintype "bidirectional"))
    )
    (net (code "55") (name "Net-(T1_6-B)") (class "Default")
      (node (ref "RS6_1") (pin "2") (pinfunction "2_2") (pintype "passive"))
      (node (ref "T1_6") (pin "G") (pinfunction "B_G") (pintype "bidirectional"))
    )
    (net (code "56") (name "Net-(T1_7-B)") (class "Default")
      (node (ref "RS3_1") (pin "2") (pinfunction "2_2") (pintype "passive"))
      (node (ref "T1_7") (pin "G") (pinfunction "B_G") (pintype "bidirectional"))
    )
    (net (code "57") (name "Net-(T1_8-B)") (class "Default")
      (node (ref "RS4_1") (pin "2") (pinfunction "2_2") (pintype "passive"))
      (node (ref "T1_8") (pin "G") (pinfunction "B_G") (pintype "bidirectional"))
    )
    (net (code "58") (name "Net-(T1_9-B)") (class "Default")
      (node (ref "RS7_1") (pin "2") (pinfunction "2_2") (pintype "passive"))
      (node (ref "T1_9") (pin "G") (pinfunction "B_G") (pintype "bidirectional"))
    )
    (net (code "59") (name "Net-(T1_10-B)") (class "Default")
      (node (ref "RS8_1") (pin "2") (pinfunction "2_2") (pintype "passive"))
      (node (ref "T1_10") (pin "G") (pinfunction "B_G") (pintype "bidirectional"))
    )
    (net (code "60") (name "Net-(T1_11-B)") (class "Default")
      (node (ref "RS9_1") (pin "2") (pinfunction "2_2") (pintype "passive"))
      (node (ref "T1_11") (pin "G") (pinfunction "B_G") (pintype "bidirectional"))
    )
    (net (code "61") (name "Net-(T1_12-B)") (class "Default")
      (node (ref "RS10_1") (pin "2") (pinfunction "2_2") (pintype "passive"))
      (node (ref "T1_12") (pin "G") (pinfunction "B_G") (pintype "bidirectional"))
    )
    (net (code "62") (name "Net-(T1_13-B)") (class "Default")
      (node (ref "RS11_1") (pin "2") (pinfunction "2_2") (pintype "passive"))
      (node (ref "T1_13") (pin "G") (pinfunction "B_G") (pintype "bidirectional"))
    )
    (net (code "63") (name "Net-(T1_14-B)") (class "Default")
      (node (ref "RS12_1") (pin "2") (pinfunction "2_2") (pintype "passive"))
      (node (ref "T1_14") (pin "G") (pinfunction "B_G") (pintype "bidirectional"))
    )
    (net (code "64") (name "Net-(U1-C0)") (class "Default")
      (node (ref "C8") (pin "1") (pinfunction "1_1") (pintype "passive"))
      (node (ref "R16") (pin "1") (pinfunction "1_1") (pintype "passive"))
      (node (ref "U1") (pin "26") (pinfunction "C0_26") (pintype "input"))
    )
    (net (code "65") (name "Net-(U1-C1)") (class "Default")
      (node (ref "C1_1") (pin "1") (pinfunction "1_1") (pintype "passive"))
      (node (ref "C2_1") (pin "2") (pinfunction "2_2") (pintype "passive"))
      (node (ref "RC1_1") (pin "1") (pinfunction "1_1") (pintype "passive"))
      (node (ref "U1") (pin "24") (pinfunction "C1_24") (pintype "input"))
    )
    (net (code "66") (name "Net-(U1-C3)") (class "Default")
      (node (ref "C3_1") (pin "1") (pinfunction "1_1") (pintype "passive"))
      (node (ref "C4_1") (pin "2") (pinfunction "2_2") (pintype "passive"))
      (node (ref "RC3_1") (pin "1") (pinfunction "1_1") (pintype "passive"))
      (node (ref "U1") (pin "20") (pinfunction "C3_20") (pintype "input"))
    )
    (net (code "67") (name "Net-(U1-C5)") (class "Default")
      (node (ref "C5_1") (pin "1") (pinfunction "1_1") (pintype "passive"))
      (node (ref "C6_1") (pin "2") (pinfunction "2_2") (pintype "passive"))
      (node (ref "RC5_1") (pin "1") (pinfunction "1_1") (pintype "passive"))
      (node (ref "U1") (pin "16") (pinfunction "C5_16") (pintype "input"))
    )
    (net (code "68") (name "Net-(U1-C7)") (class "Default")
      (node (ref "C7_1") (pin "1") (pinfunction "1_1") (pintype "passive"))
      (node (ref "C8_1") (pin "2") (pinfunction "2_2") (pintype "passive"))
      (node (ref "RC7_1") (pin "1") (pinfunction "1_1") (pintype "passive"))
      (node (ref "U1") (pin "12") (pinfunction "C7_12") (pintype "input"))
    )
    (net (code "69") (name "Net-(U1-C9)") (class "Default")
      (node (ref "C10_1") (pin "2") (pinfunction "2_2") (pintype "passive"))
      (node (ref "C9_1") (pin "1") (pinfunction "1_1") (pintype "passive"))
      (node (ref "RC9_1") (pin "1") (pinfunction "1_1") (pintype "passive"))
      (node (ref "U1") (pin "8") (pinfunction "C9_8") (pintype "input"))
    )
    (net (code "70") (name "Net-(U1-C10)") (class "Default")
      (node (ref "C10_1") (pin "1") (pinfunction "1_1") (pintype "passive"))
      (node (ref "C11_1") (pin "2") (pinfunction "2_2") (pintype "passive"))
      (node (ref "RC10_1") (pin "1") (pinfunction "1_1") (pintype "passive"))
      (node (ref "U1") (pin "6") (pinfunction "C10_6") (pintype "input"))
    )
    (net (code "71") (name "Net-(U1-C11)") (class "Default")
      (node (ref "C11_1") (pin "1") (pinfunction "1_1") (pintype "passive"))
      (node (ref "C12_1") (pin "2") (pinfunction "2_2") (pintype "passive"))
      (node (ref "RC11_1") (pin "1") (pinfunction "1_1") (pintype "passive"))
      (node (ref "U1") (pin "4") (pinfunction "C11_4") (pintype "input"))
    )
    (net (code "72") (name "Net-(U1-C12)") (class "Default")
      (node (ref "C12_1") (pin "1") (pinfunction "1_1") (pintype "passive"))
      (node (ref "RC12_1") (pin "1") (pinfunction "1_1") (pintype "passive"))
      (node (ref "U1") (pin "2") (pinfunction "C12_2") (pintype "input"))
    )
    (net (code "73") (name "Net-(U1-CSB{slash}IMA)") (class "Default")
      (node (ref "JP1") (pin "2") (pinfunction "2_2") (pintype "passive"))
      (node (ref "U1") (pin "41") (pinfunction "CSB/IMA_41") (pintype "input"))
    )
    (net (code "74") (name "Net-(U1-DRIVE)") (class "Default")
      (node (ref "DZT5551-13") (pin "B") (pinfunction "B_B") (pintype "bidirectional"))
      (node (ref "U1") (pin "38") (pinfunction "DRIVE_38") (pintype "output"))
    )
    (net (code "75") (name "Net-(U1-DTEN)") (class "Default")
      (node (ref "JP4") (pin "2") (pinfunction "2_2") (pintype "passive"))
      (node (ref "U1") (pin "36") (pinfunction "DTEN_36") (pintype "input"))
    )
    (net (code "76") (name "Net-(U1-IBIAS)") (class "Default")
      (node (ref "R1") (pin "2") (pinfunction "2_2") (pintype "passive"))
      (node (ref "U1") (pin "45") (pinfunction "IBIAS_45") (pintype "input"))
    )
    (net (code "77") (name "Net-(U1-ICMP)") (class "Default")
      (node (ref "R1") (pin "1") (pinfunction "1_1") (pintype "passive"))
      (node (ref "R2") (pin "2") (pinfunction "2_2") (pintype "passive"))
      (node (ref "U1") (pin "46") (pinfunction "ICMP_46") (pintype "input"))
    )
    (net (code "78") (name "Net-(U1-IMB)") (class "Default")
      (node (ref "R6") (pin "1") (pinfunction "1_1") (pintype "passive"))
      (node (ref "U$1") (pin "9") (pinfunction "9_9") (pintype "bidirectional"))
      (node (ref "U1") (pin "47") (pinfunction "IMB_47") (pintype "input"))
    )
    (net (code "79") (name "Net-(U1-IPB)") (class "Default")
      (node (ref "R6") (pin "2") (pinfunction "2_2") (pintype "passive"))
      (node (ref "U$1") (pin "7") (pinfunction "7_7") (pintype "bidirectional"))
      (node (ref "U1") (pin "48") (pinfunction "IPB_48") (pintype "input"))
    )
    (net (code "80") (name "Net-(U1-ISOMD)") (class "Default")
      (node (ref "JP3") (pin "2") (pinfunction "2_2") (pintype "passive"))
      (node (ref "U1") (pin "40") (pinfunction "ISOMD_40") (pintype "input"))
    )
    (net (code "81") (name "Net-(U1-S1)") (class "Default")
      (node (ref "RS1_1") (pin "1") (pinfunction "1_1") (pintype "passive"))
      (node (ref "U1") (pin "25") (pinfunction "S1_25") (pintype "bidirectional"))
    )
    (net (code "82") (name "Net-(U1-S2)") (class "Default")
      (node (ref "RS2_1") (pin "1") (pinfunction "1_1") (pintype "passive"))
      (node (ref "U1") (pin "23") (pinfunction "S2_23") (pintype "bidirectional"))
    )
    (net (code "83") (name "Net-(U1-S3)") (class "Default")
      (node (ref "RS3_1") (pin "1") (pinfunction "1_1") (pintype "passive"))
      (node (ref "U1") (pin "21") (pinfunction "S3_21") (pintype "bidirectional"))
    )
    (net (code "84") (name "Net-(U1-S4)") (class "Default")
      (node (ref "RS4_1") (pin "1") (pinfunction "1_1") (pintype "passive"))
      (node (ref "U1") (pin "19") (pinfunction "S4_19") (pintype "bidirectional"))
    )
    (net (code "85") (name "Net-(U1-S5)") (class "Default")
      (node (ref "RS5_1") (pin "1") (pinfunction "1_1") (pintype "passive"))
      (node (ref "U1") (pin "17") (pinfunction "S5_17") (pintype "bidirectional"))
    )
    (net (code "86") (name "Net-(U1-S6)") (class "Default")
      (node (ref "RS6_1") (pin "1") (pinfunction "1_1") (pintype "passive"))
      (node (ref "U1") (pin "15") (pinfunction "S6_15") (pintype "bidirectional"))
    )
    (net (code "87") (name "Net-(U1-S7)") (class "Default")
      (node (ref "RS7_1") (pin "1") (pinfunction "1_1") (pintype "passive"))
      (node (ref "U1") (pin "13") (pinfunction "S7_13") (pintype "bidirectional"))
    )
    (net (code "88") (name "Net-(U1-S8)") (class "Default")
      (node (ref "RS8_1") (pin "1") (pinfunction "1_1") (pintype "passive"))
      (node (ref "U1") (pin "11") (pinfunction "S8_11") (pintype "bidirectional"))
    )
    (net (code "89") (name "Net-(U1-S9)") (class "Default")
      (node (ref "RS9_1") (pin "1") (pinfunction "1_1") (pintype "passive"))
      (node (ref "U1") (pin "9") (pinfunction "S9_9") (pintype "bidirectional"))
    )
    (net (code "90") (name "Net-(U1-S10)") (class "Default")
      (node (ref "RS10_1") (pin "1") (pinfunction "1_1") (pintype "passive"))
      (node (ref "U1") (pin "7") (pinfunction "S10_7") (pintype "bidirectional"))
    )
    (net (code "91") (name "Net-(U1-S11)") (class "Default")
      (node (ref "RS11_1") (pin "1") (pinfunction "1_1") (pintype "passive"))
      (node (ref "U1") (pin "5") (pinfunction "S11_5") (pintype "bidirectional"))
    )
    (net (code "92") (name "Net-(U1-S12)") (class "Default")
      (node (ref "RS12_1") (pin "1") (pinfunction "1_1") (pintype "passive"))
      (node (ref "U1") (pin "3") (pinfunction "S12_3") (pintype "bidirectional"))
    )
    (net (code "93") (name "Net-(U1-SCK{slash}IPA)") (class "Default")
      (node (ref "JP2") (pin "2") (pinfunction "2_2") (pintype "passive"))
      (node (ref "U1") (pin "42") (pinfunction "SCK/IPA_42") (pintype "input"))
    )
    (net (code "94") (name "Net-(U1-V+)") (class "Default")
      (node (ref "C1") (pin "1") (pinfunction "1_1") (pintype "passive"))
      (node (ref "R3") (pin "1") (pinfunction "1_1") (pintype "passive"))
      (node (ref "U1") (pin "1") (pinfunction "V+_1") (pintype "power_in"))
    )
    (net (code "95") (name "Net-(U1-VREF1)") (class "Default")
      (node (ref "C4") (pin "1") (pinfunction "1_1") (pintype "passive"))
      (node (ref "U1") (pin "35") (pinfunction "VREF1_35") (pintype "power_in"))
    )
    (net (code "96") (name "Net-(U1-VREF2)") (class "Default")
      (node (ref "C5") (pin "1") (pinfunction "1_1") (pintype "passive"))
      (node (ref "U1") (pin "34") (pinfunction "VREF2_34") (pintype "power_in"))
    )
    (net (code "97") (name "Net-(U1-VREG)") (class "Default")
      (node (ref "C3") (pin "1") (pinfunction "1_1") (pintype "passive"))
      (node (ref "DZT5551-13") (pin "E") (pinfunction "E_E") (pintype "bidirectional"))
      (node (ref "JP3") (pin "1") (pinfunction "1_1") (pintype "passive"))
      (node (ref "JP4") (pin "1") (pinfunction "1_1") (pintype "passive"))
      (node (ref "R5") (pin "1") (pinfunction "1_1") (pintype "passive"))
      (node (ref "R7") (pin "1") (pinfunction "1_1") (pintype "passive"))
      (node (ref "R8") (pin "1") (pinfunction "1_1") (pintype "passive"))
      (node (ref "U1") (pin "37") (pinfunction "VREG_37") (pintype "power_in"))
    )
    (net (code "98") (name "SCK") (class "Default")
      (node (ref "JP2") (pin "3") (pinfunction "3_3") (pintype "passive"))
      (node (ref "MOLEX_SL_5") (pin "1") (pinfunction "1_1") (pintype "passive"))
      (node (ref "R5") (pin "2") (pinfunction "2_2") (pintype "passive"))
    )
    (net (code "99") (name "SDI") (class "Default")
      (node (ref "MOLEX_SL_5") (pin "4") (pinfunction "4_4") (pintype "passive"))
      (node (ref "R7") (pin "2") (pinfunction "2_2") (pintype "passive"))
      (node (ref "U1") (pin "43") (pinfunction "SDI/MC_43") (pintype "input"))
    )
    (net (code "100") (name "SDO") (class "Default")
      (node (ref "MOLEX_SL_5") (pin "3") (pinfunction "3_3") (pintype "passive"))
      (node (ref "U1") (pin "44") (pinfunction "SDO/NC_44") (pintype "output"))
    )
    (net (code "101") (name "V-_1") (class "Default")
      (node (ref "C1") (pin "2") (pinfunction "2_2") (pintype "passive"))
      (node (ref "C2") (pin "2") (pinfunction "2_2") (pintype "passive"))
      (node (ref "C3") (pin "2") (pinfunction "2_2") (pintype "passive"))
      (node (ref "C4") (pin "2") (pinfunction "2_2") (pintype "passive"))
      (node (ref "C5") (pin "2") (pinfunction "2_2") (pintype "passive"))
      (node (ref "C6") (pin "2") (pinfunction "2_2") (pintype "passive"))
      (node (ref "C7") (pin "2") (pinfunction "2_2") (pintype "passive"))
      (node (ref "C8") (pin "2") (pinfunction "2_2") (pintype "passive"))
      (node (ref "JP3") (pin "3") (pinfunction "3_3") (pintype "passive"))
      (node (ref "JP4") (pin "3") (pinfunction "3_3") (pintype "passive"))
      (node (ref "L1") (pin "2") (pinfunction "2_2") (pintype "passive"))
      (node (ref "MOLEX_SL_5") (pin "5") (pinfunction "5_5") (pintype "passive"))
      (node (ref "R2") (pin "1") (pinfunction "1_1") (pintype "passive"))
      (node (ref "U1") (pin "30") (pinfunction "V-_30") (pintype "power_in"))
      (node (ref "U1") (pin "31") (pinfunction "V-_31") (pintype "power_in"))
    )
    (net (code "102") (name "XOUT1_1") (class "Default")
      (node (ref "MOLEX_SL_2") (pin "2") (pinfunction "2_2") (pintype "passive"))
      (node (ref "U$1") (pin "1") (pinfunction "1_1") (pintype "bidirectional"))
    )
    (net (code "103") (name "XOUT3_1") (class "Default")
      (node (ref "MOLEX_SL_2") (pin "1") (pinfunction "1_1") (pintype "passive"))
      (node (ref "U$1") (pin "3") (pinfunction "3_3") (pintype "bidirectional"))
    )
    (net (code "104") (name "unconnected-(C1_1-Pad2)") (class "Default")
      (node (ref "C1_1") (pin "2") (pinfunction "2_2") (pintype "passive"))
    )
    (net (code "105") (name "unconnected-(U$1-Pad2)") (class "Default")
      (node (ref "U$1") (pin "2") (pinfunction "2_2") (pintype "bidirectional"))
    )
    (net (code "106") (name "unconnected-(U$1-Pad5)") (class "Default")
      (node (ref "U$1") (pin "5") (pinfunction "5_5") (pintype "bidirectional"))
    )
    (net (code "107") (name "unconnected-(U1-GPIO1-Pad27)") (class "Default")
      (node (ref "U1") (pin "27") (pinfunction "GPIO1_27") (pintype "bidirectional"))
    )
    (net (code "108") (name "unconnected-(U1-GPIO2-Pad28)") (class "Default")
      (node (ref "U1") (pin "28") (pinfunction "GPIO2_28") (pintype "bidirectional"))
    )
    (net (code "109") (name "unconnected-(U1-GPIO3-Pad29)") (class "Default")
      (node (ref "U1") (pin "29") (pinfunction "GPIO3_29") (pintype "bidirectional"))
    )
    (net (code "110") (name "unconnected-(U1-GPIO4-Pad32)") (class "Default")
      (node (ref "U1") (pin "32") (pinfunction "GPIO4_32") (pintype "bidirectional"))
    )
    (net (code "111") (name "unconnected-(U1-GPIO5-Pad33)") (class "Default")
      (node (ref "U1") (pin "33") (pinfunction "GPIO5_33") (pintype "bidirectional"))
    )
    (net (code "112") (name "unconnected-(U1-WDT-Pad39)") (class "Default")
      (node (ref "U1") (pin "39") (pinfunction "WDT_39") (pintype "output"))
    )
  )
)
